# 3_AT_START_F403A_V1_2_PowerPeripherals.net
KiCad netlist of a schematic drawn in Altium Designer
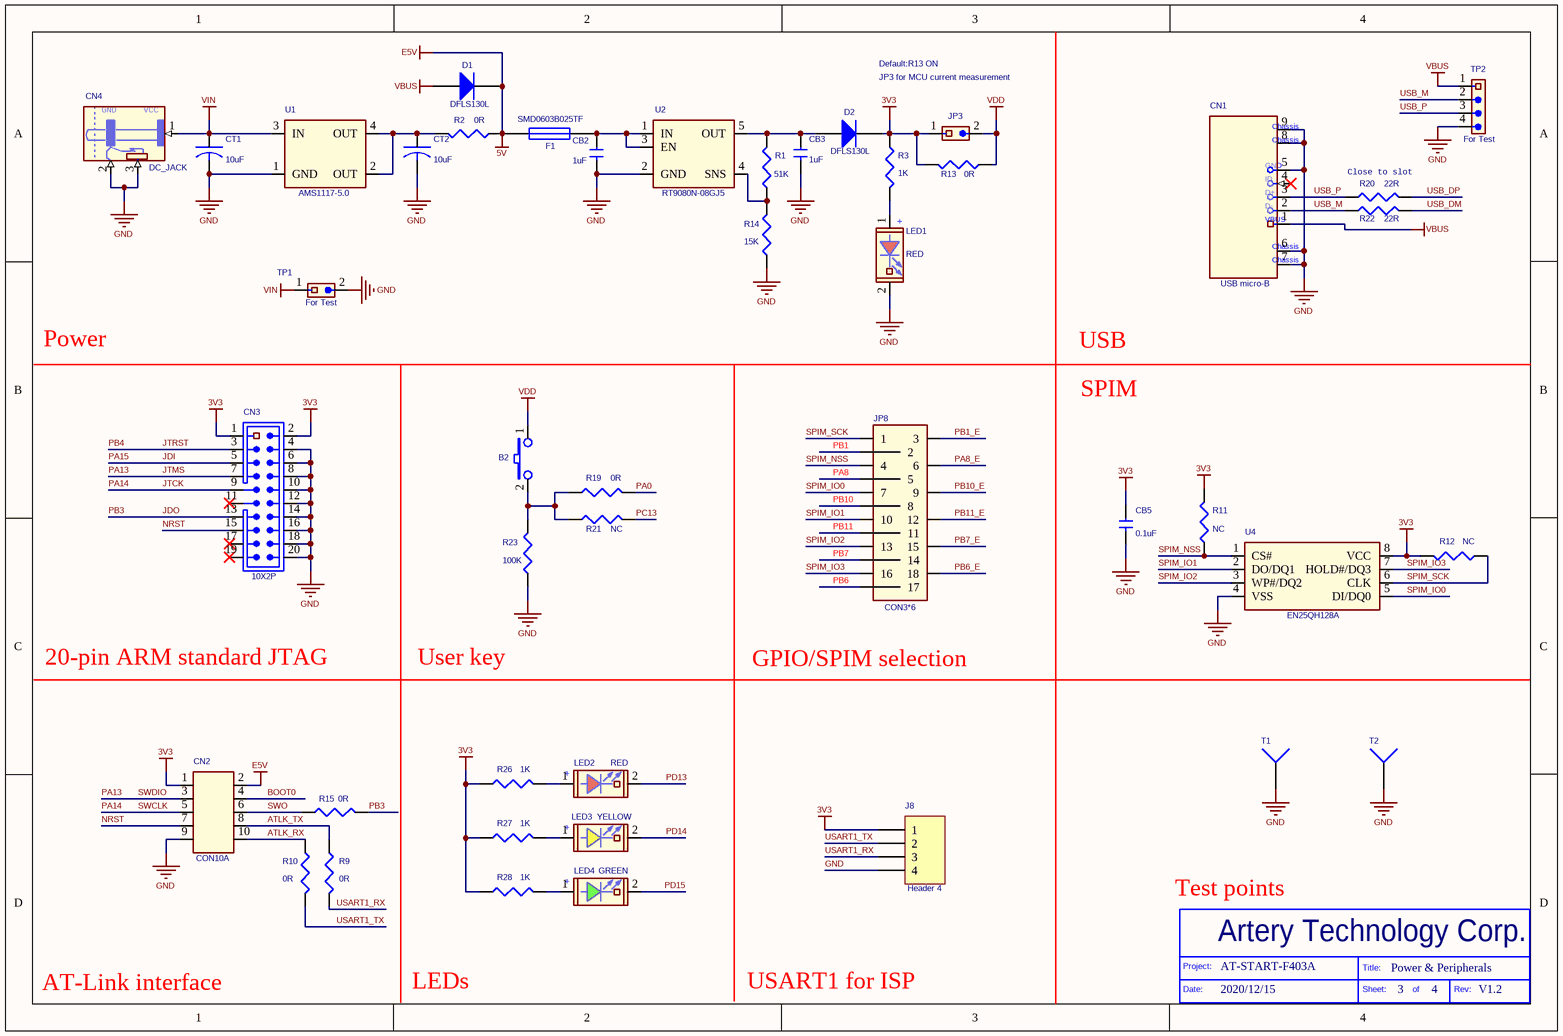
[diagram p0: 3_AT_START_F403A_V1.2_PowerPeripherals.SchDoc]

(export (version "E")
  (design (tool "Eeschema 10.0.6"))
  (components
    (comp (ref "B2") (value "PB,Blue,SMD_2P") (libsource (lib "*") (part "Push_Bottom,Blue,SMD_2P")))
    (comp (ref "CB2") (value "1uF") (libsource (lib "*") (part "0.1uF,50V,20%,SMD0603")))
    (comp (ref "CB3") (value "1uF") (libsource (lib "*") (part "0.1uF,50V,20%,SMD0603")))
    (comp (ref "CB5") (value "0.1uF") (libsource (lib "*") (part "10uF,10V,10%,SMD0603")))
    (comp (ref "CN1") (value "USB micro-B") (libsource (lib "*") (part "USB_miniAB,SMD_0")))
    (comp (ref "CN2") (value "CON10A") (footprint "HDR2X5") (libsource (lib "*") (part "CON10A_0")))
    (comp (ref "CN3") (value "10X2P") (libsource (lib "*") (part "10x2P,Male,Housing,DIP_2.54")))
    (comp (ref "CN4") (value "DC_JACK") (libsource (lib "*") (part "DC12V_Power_JACK,2.0,DIP_3P")))
    (comp (ref "CT1")
      (value "10uF")
      (description "10uF,10%,25V")
      (libsource (lib "*") (part "10uF,16V,20%,B_Case_Dup1"))
    )
    (comp (ref "CT2")
      (value "10uF")
      (description "10uF,10%,25V")
      (libsource (lib "*") (part "10uF,16V,20%,B_Case_Dup1"))
    )
    (comp (ref "D1")
      (value "DFLS130L")
      (footprint "SOD-123")
      (description "Default Diode")
      (fields (field (name "PUBLISHER") "Altium Limited"))
      (libsource (lib "Miscellaneous Devices") (part "Diode"))
    )
    (comp (ref "D2")
      (value "DFLS130L")
      (footprint "SOD-123")
      (description "Default Diode")
      (fields (field (name "PUBLISHER") "Altium Limited"))
      (libsource (lib "Miscellaneous Devices") (part "Diode"))
    )
    (comp (ref "F1")
      (value "SMD0603B025TF")
      (footprint "r0603")
      (description "Fuse")
      (fields (field (name "PUBLISHER") "Altium Limited"))
      (libsource (lib "Miscellaneous Devices") (part "Fuse 1"))
    )
    (comp (ref "J8")
      (value "Header 4")
      (footprint "HDR1X4")
      (description "Header, 4-Pin")
      (fields (field (name "PUBLISHER") "Altium Limited"))
      (libsource (lib "Miscellaneous Connectors") (part "Header 4"))
    )
    (comp (ref "JP3")
      (value "1X2P_2.54M")
      (footprint "HDR1X2")
      (libsource (lib "*") (part "1X2P,Male,DIP_2.54"))
    )
    (comp (ref "JP8")
      (value "CON3*6")
      (footprint "HDR3X6")
      (libsource (lib "SCM_START_402F") (part "CON3*6"))
    )
    (comp (ref "LED1") (value "RED") (footprint "LED0603") (libsource (lib "") (part "RED,SMD0603_1")))
    (comp (ref "LED2")
      (value "RED")
      (footprint "LED0603")
      (libsource (lib "AT32F403_TINY_LQFP144_Library") (part "RED,SMD0603"))
    )
    (comp (ref "LED3")
      (value "YELLOW")
      (footprint "LED0603")
      (libsource (lib "Schlib1") (part "YELLOW,SMD0603"))
    )
    (comp (ref "LED4")
      (value "GREEN")
      (footprint "LED0603")
      (libsource (lib "AT32F403_TINY_LQFP144_Library") (part "GREEN,SMD0603"))
    )
    (comp (ref "R1") (value "51K") (libsource (lib "*") (part "470,1/10W,1%,SMD0603")))
    (comp (ref "R2") (value "0R") (libsource (lib "*") (part "470,1/10W,1%,SMD0603")))
    (comp (ref "R3") (value "1K") (libsource (lib "*") (part "470,1/10W,1%,SMD0603")))
    (comp (ref "R9") (value "0R") (libsource (lib "*") (part "470,1/10W,1%,SMD0603")))
    (comp (ref "R10") (value "0R") (libsource (lib "*") (part "470,1/10W,1%,SMD0603")))
    (comp (ref "R11") (value "NC") (libsource (lib "*") (part "47K,1/10W,1%,SMD0603")))
    (comp (ref "R12") (value "NC") (libsource (lib "*") (part "47K,1/10W,1%,SMD0603")))
    (comp (ref "R13") (value "0R") (libsource (lib "*") (part "470,1/10W,1%,SMD0603")))
    (comp (ref "R14") (value "15K") (libsource (lib "*") (part "470,1/10W,1%,SMD0603")))
    (comp (ref "R15") (value "0R") (libsource (lib "*") (part "470,1/10W,1%,SMD0603")))
    (comp (ref "R19") (value "0R") (libsource (lib "*") (part "470,1/10W,1%,SMD0603")))
    (comp (ref "R20") (value "22R") (libsource (lib "*") (part "22,1/10W,1%,SMD0603")))
    (comp (ref "R21") (value "NC") (libsource (lib "*") (part "470,1/10W,1%,SMD0603")))
    (comp (ref "R22") (value "22R") (libsource (lib "*") (part "22,1/10W,1%,SMD0603")))
    (comp (ref "R23") (value "100K") (libsource (lib "*") (part "10K,1/10W,1%,SMD0603")))
    (comp (ref "R26") (value "1K") (libsource (lib "*") (part "470,1/10W,1%,SMD0603")))
    (comp (ref "R27") (value "1K") (libsource (lib "*") (part "470,1/10W,1%,SMD0603")))
    (comp (ref "R28") (value "1K") (libsource (lib "*") (part "470,1/10W,1%,SMD0603")))
    (comp (ref "T1")
      (value "Socket")
      (footprint "TestPoint")
      (fields (field (name "PUBLISHER") "Altium Limited"))
      (libsource (lib "Miscellaneous Connectors") (part "Socket"))
    )
    (comp (ref "T2")
      (value "Socket")
      (footprint "TestPoint")
      (fields (field (name "PUBLISHER") "Altium Limited"))
      (libsource (lib "Miscellaneous Connectors") (part "Socket"))
    )
    (comp (ref "TP1")
      (value "1X2P_2.54M")
      (footprint "HDR1X2 - SOP")
      (libsource (lib "*") (part "1X2P,Male,DIP_2.54"))
    )
    (comp (ref "TP2")
      (value "1X4P_2.54F")
      (footprint "HDR1X4 - top")
      (libsource (lib "*") (part "1X4P,Female,DIP_2.54"))
    )
    (comp (ref "U1") (value "AMS1117-5.0") (libsource (lib "*") (part "AMS1117-3.3")))
    (comp (ref "U2") (value "RT9080N-08GJ5") (libsource (lib "SCM_START_402F") (part "RT9080N")))
    (comp (ref "U4")
      (value "EN25QH128A")
      (footprint "SOIC8_208")
      (libsource (lib "AT32F403_TINY_LQFP144_Library") (part "W25Q128FVSIQ,SOIC8_1"))
    )
  )
  (nets
    (net (code "1") (name "/ATLK_RX") (class "Default")
      (node (ref "CN2") (pin "10") (pinfunction "10_10") (pintype "passive"))
      (node (ref "R10") (pin "1") (pinfunction "1_1") (pintype "passive"))
    )
    (net (code "2") (name "/ATLK_TX") (class "Default")
      (node (ref "CN2") (pin "8") (pinfunction "8_8") (pintype "passive"))
      (node (ref "R9") (pin "1") (pinfunction "1_1") (pintype "passive"))
    )
    (net (code "3") (name "/BOOT0") (class "Default")
      (node (ref "CN2") (pin "4") (pinfunction "4_4") (pintype "passive"))
    )
    (net (code "4") (name "/JDI") (class "Default")
      (node (ref "CN3") (pin "5") (pinfunction "5_5") (pintype "passive"))
    )
    (net (code "5") (name "/JDO") (class "Default")
      (node (ref "CN3") (pin "13") (pinfunction "13_13") (pintype "passive"))
      (node (ref "R15") (pin "2") (pinfunction "2_2") (pintype "passive"))
    )
    (net (code "6") (name "/JTCK") (class "Default")
      (node (ref "CN2") (pin "5") (pinfunction "5_5") (pintype "passive"))
      (node (ref "CN3") (pin "9") (pinfunction "9_9") (pintype "passive"))
    )
    (net (code "7") (name "/JTMS") (class "Default")
      (node (ref "CN2") (pin "3") (pinfunction "3_3") (pintype "passive"))
      (node (ref "CN3") (pin "7") (pinfunction "7_7") (pintype "passive"))
    )
    (net (code "8") (name "/JTRST") (class "Default")
      (node (ref "CN3") (pin "3") (pinfunction "3_3") (pintype "passive"))
    )
    (net (code "9") (name "/NRST") (class "Default")
      (node (ref "CN2") (pin "7") (pinfunction "7_7") (pintype "passive"))
      (node (ref "CN3") (pin "15") (pinfunction "15_15") (pintype "passive"))
    )
    (net (code "10") (name "/PA0") (class "Default")
      (node (ref "R19") (pin "2") (pinfunction "2_2") (pintype "passive"))
    )
    (net (code "11") (name "/PA8") (class "Default")
      (node (ref "JP8") (pin "5") (pinfunction "5_5") (pintype "passive"))
    )
    (net (code "12") (name "/PA8_E") (class "Default")
      (node (ref "JP8") (pin "6") (pinfunction "6_6") (pintype "passive"))
    )
    (net (code "13") (name "/PB1") (class "Default")
      (node (ref "JP8") (pin "2") (pinfunction "2_2") (pintype "passive"))
    )
    (net (code "14") (name "/PB1_E") (class "Default")
      (node (ref "JP8") (pin "3") (pinfunction "3_3") (pintype "passive"))
    )
    (net (code "15") (name "/PB6") (class "Default")
      (node (ref "JP8") (pin "17") (pinfunction "17_17") (pintype "passive"))
    )
    (net (code "16") (name "/PB6_E") (class "Default")
      (node (ref "JP8") (pin "18") (pinfunction "18_18") (pintype "passive"))
    )
    (net (code "17") (name "/PB7") (class "Default")
      (node (ref "JP8") (pin "14") (pinfunction "14_14") (pintype "passive"))
    )
    (net (code "18") (name "/PB7_E") (class "Default")
      (node (ref "JP8") (pin "15") (pinfunction "15_15") (pintype "passive"))
    )
    (net (code "19") (name "/PB10") (class "Default")
      (node (ref "JP8") (pin "8") (pinfunction "8_8") (pintype "passive"))
    )
    (net (code "20") (name "/PB10_E") (class "Default")
      (node (ref "JP8") (pin "9") (pinfunction "9_9") (pintype "passive"))
    )
    (net (code "21") (name "/PB11") (class "Default")
      (node (ref "JP8") (pin "11") (pinfunction "11_11") (pintype "passive"))
    )
    (net (code "22") (name "/PB11_E") (class "Default")
      (node (ref "JP8") (pin "12") (pinfunction "12_12") (pintype "passive"))
    )
    (net (code "23") (name "/PC13") (class "Default")
      (node (ref "R21") (pin "2") (pinfunction "2_2") (pintype "passive"))
    )
    (net (code "24") (name "/PD13") (class "Default")
      (node (ref "LED2") (pin "2") (pinfunction "CATHODE_2") (pintype "passive"))
    )
    (net (code "25") (name "/PD14") (class "Default")
      (node (ref "LED3") (pin "2") (pinfunction "CATHODE_2") (pintype "passive"))
    )
    (net (code "26") (name "/PD15") (class "Default")
      (node (ref "LED4") (pin "2") (pinfunction "CATHODE_2") (pintype "passive"))
    )
    (net (code "27") (name "/SPIM_IO0") (class "Default")
      (node (ref "JP8") (pin "7") (pinfunction "7_7") (pintype "passive"))
      (node (ref "U4") (pin "5") (pinfunction "DI/DQ0_5") (pintype "passive"))
    )
    (net (code "28") (name "/SPIM_IO1") (class "Default")
      (node (ref "JP8") (pin "10") (pinfunction "10_10") (pintype "passive"))
      (node (ref "U4") (pin "2") (pinfunction "DO/DQ1_2") (pintype "passive"))
    )
    (net (code "29") (name "/SPIM_IO2") (class "Default")
      (node (ref "JP8") (pin "13") (pinfunction "13_13") (pintype "passive"))
      (node (ref "U4") (pin "3") (pinfunction "WP#/DQ2_3") (pintype "passive"))
    )
    (net (code "30") (name "/SPIM_IO3") (class "Default")
      (node (ref "JP8") (pin "16") (pinfunction "16_16") (pintype "passive"))
      (node (ref "U4") (pin "7") (pinfunction "HOLD#/DQ3_7") (pintype "passive"))
    )
    (net (code "31") (name "/SPIM_NSS") (class "Default")
      (node (ref "JP8") (pin "4") (pinfunction "4_4") (pintype "passive"))
      (node (ref "R11") (pin "1") (pinfunction "1_1") (pintype "passive"))
      (node (ref "U4") (pin "1") (pinfunction "CS#_1") (pintype "passive"))
    )
    (net (code "32") (name "/SPIM_SCK") (class "Default")
      (node (ref "JP8") (pin "1") (pinfunction "1_1") (pintype "passive"))
      (node (ref "R12") (pin "1") (pinfunction "1_1") (pintype "passive"))
      (node (ref "U4") (pin "6") (pinfunction "CLK_6") (pintype "passive"))
    )
    (net (code "33") (name "/SWO") (class "Default")
      (node (ref "CN2") (pin "6") (pinfunction "6_6") (pintype "passive"))
      (node (ref "R15") (pin "1") (pinfunction "1_1") (pintype "passive"))
    )
    (net (code "34") (name "/USART1_RX") (class "Default")
      (node (ref "J8") (pin "3") (pinfunction "3_3") (pintype "passive"))
      (node (ref "R9") (pin "2") (pinfunction "2_2") (pintype "passive"))
    )
    (net (code "35") (name "/USART1_TX") (class "Default")
      (node (ref "J8") (pin "2") (pinfunction "2_2") (pintype "passive"))
      (node (ref "R10") (pin "2") (pinfunction "2_2") (pintype "passive"))
    )
    (net (code "36") (name "/USB_DM") (class "Default")
      (node (ref "R22") (pin "2") (pinfunction "2_2") (pintype "passive"))
    )
    (net (code "37") (name "/USB_DP") (class "Default")
      (node (ref "R20") (pin "2") (pinfunction "2_2") (pintype "passive"))
    )
    (net (code "38") (name "/USB_M") (class "Default")
      (node (ref "CN1") (pin "2") (pinfunction "D-_2") (pintype "bidirectional"))
      (node (ref "R22") (pin "1") (pinfunction "1_1") (pintype "passive"))
      (node (ref "TP2") (pin "2") (pinfunction "2_2") (pintype "passive"))
    )
    (net (code "39") (name "/USB_P") (class "Default")
      (node (ref "CN1") (pin "3") (pinfunction "D+_3") (pintype "bidirectional"))
      (node (ref "R20") (pin "1") (pinfunction "1_1") (pintype "passive"))
      (node (ref "TP2") (pin "3") (pinfunction "3_3") (pintype "passive"))
    )
    (net (code "40") (name "3V3") (class "Default")
      (node (ref "CB5") (pin "1") (pinfunction "1_1") (pintype "passive"))
      (node (ref "CN2") (pin "1") (pinfunction "1_1") (pintype "passive"))
      (node (ref "CN3") (pin "1") (pinfunction "1_1") (pintype "passive"))
      (node (ref "CN3") (pin "2") (pinfunction "2_2") (pintype "passive"))
      (node (ref "D2") (pin "2") (pinfunction "K_2") (pintype "passive"))
      (node (ref "J8") (pin "1") (pinfunction "1_1") (pintype "passive"))
      (node (ref "JP3") (pin "1") (pinfunction "1_1") (pintype "passive"))
      (node (ref "R11") (pin "2") (pinfunction "2_2") (pintype "passive"))
      (node (ref "R12") (pin "2") (pinfunction "2_2") (pintype "passive"))
      (node (ref "R13") (pin "2") (pinfunction "2_2") (pintype "passive"))
      (node (ref "R26") (pin "1") (pinfunction "1_1") (pintype "passive"))
      (node (ref "R27") (pin "1") (pinfunction "1_1") (pintype "passive"))
      (node (ref "R28") (pin "1") (pinfunction "1_1") (pintype "passive"))
      (node (ref "R3") (pin "1") (pinfunction "1_1") (pintype "passive"))
      (node (ref "U4") (pin "8") (pinfunction "VCC_8") (pintype "power_in"))
    )
    (net (code "41") (name "5V") (class "Default")
      (node (ref "CN2") (pin "2") (pinfunction "2_2") (pintype "passive"))
      (node (ref "D1") (pin "2") (pinfunction "K_2") (pintype "passive"))
      (node (ref "F1") (pin "1") (pinfunction "1_1") (pintype "passive"))
      (node (ref "R2") (pin "1") (pinfunction "1_1") (pintype "passive"))
    )
    (net (code "42") (name "GND") (class "Default")
      (node (ref "CB2") (pin "2") (pinfunction "2_2") (pintype "passive"))
      (node (ref "CB3") (pin "2") (pinfunction "2_2") (pintype "passive"))
      (node (ref "CB5") (pin "2") (pinfunction "2_2") (pintype "passive"))
      (node (ref "CN1") (pin "5") (pinfunction "GND_5") (pintype "passive"))
      (node (ref "CN1") (pin "6") (pinfunction "6_6") (pintype "passive"))
      (node (ref "CN1") (pin "7") (pinfunction "7_7") (pintype "passive"))
      (node (ref "CN1") (pin "8") (pinfunction "8_8") (pintype "passive"))
      (node (ref "CN1") (pin "9") (pinfunction "9_9") (pintype "passive"))
      (node (ref "CN2") (pin "9") (pinfunction "9_9") (pintype "passive"))
      (node (ref "CN3") (pin "10") (pinfunction "10_10") (pintype "passive"))
      (node (ref "CN3") (pin "12") (pinfunction "12_12") (pintype "passive"))
      (node (ref "CN3") (pin "14") (pinfunction "14_14") (pintype "passive"))
      (node (ref "CN3") (pin "16") (pinfunction "16_16") (pintype "passive"))
      (node (ref "CN3") (pin "18") (pinfunction "18_18") (pintype "passive"))
      (node (ref "CN3") (pin "20") (pinfunction "20_20") (pintype "passive"))
      (node (ref "CN3") (pin "4") (pinfunction "4_4") (pintype "passive"))
      (node (ref "CN3") (pin "6") (pinfunction "6_6") (pintype "passive"))
      (node (ref "CN3") (pin "8") (pinfunction "8_8") (pintype "passive"))
      (node (ref "CN4") (pin "2") (pinfunction "2_2") (pintype "input"))
      (node (ref "CN4") (pin "3") (pinfunction "3_3") (pintype "input"))
      (node (ref "CT1") (pin "2") (pinfunction "2_2") (pintype "passive"))
      (node (ref "CT2") (pin "2") (pinfunction "2_2") (pintype "passive"))
      (node (ref "J8") (pin "4") (pinfunction "4_4") (pintype "passive"))
      (node (ref "LED1") (pin "2") (pinfunction "CATHODE_2") (pintype "passive"))
      (node (ref "R14") (pin "1") (pinfunction "1_1") (pintype "passive"))
      (node (ref "R23") (pin "1") (pinfunction "1_1") (pintype "passive"))
      (node (ref "T1") (pin "1") (pinfunction "1_1") (pintype "passive"))
      (node (ref "T2") (pin "1") (pinfunction "1_1") (pintype "passive"))
      (node (ref "TP1") (pin "2") (pinfunction "2_2") (pintype "passive"))
      (node (ref "TP2") (pin "4") (pinfunction "4_4") (pintype "passive"))
      (node (ref "U1") (pin "1") (pinfunction "GND_1") (pintype "passive"))
      (node (ref "U2") (pin "2") (pinfunction "GND_2") (pintype "power_in"))
      (node (ref "U4") (pin "4") (pinfunction "VSS_4") (pintype "power_in"))
    )
    (net (code "43") (name "Net-(B2-Pad2)") (class "Default")
      (node (ref "B2") (pin "2") (pinfunction "2_2") (pintype "passive"))
      (node (ref "R19") (pin "1") (pinfunction "1_1") (pintype "passive"))
      (node (ref "R21") (pin "1") (pinfunction "1_1") (pintype "passive"))
      (node (ref "R23") (pin "2") (pinfunction "2_2") (pintype "passive"))
    )
    (net (code "44") (name "Net-(CT2-Pad1)") (class "Default")
      (node (ref "CT2") (pin "1") (pinfunction "1_1") (pintype "passive"))
      (node (ref "R2") (pin "2") (pinfunction "2_2") (pintype "passive"))
      (node (ref "U1") (pin "2") (pinfunction "OUT_2") (pintype "passive"))
      (node (ref "U1") (pin "4") (pinfunction "OUT_4") (pintype "passive"))
    )
    (net (code "45") (name "Net-(D2-A)") (class "Default")
      (node (ref "CB3") (pin "1") (pinfunction "1_1") (pintype "passive"))
      (node (ref "D2") (pin "1") (pinfunction "A_1") (pintype "passive"))
      (node (ref "R1") (pin "2") (pinfunction "2_2") (pintype "passive"))
      (node (ref "U2") (pin "5") (pinfunction "OUT_5") (pintype "power_in"))
    )
    (net (code "46") (name "Net-(LED1-ANODE)") (class "Default")
      (node (ref "LED1") (pin "1") (pinfunction "ANODE_1") (pintype "passive"))
      (node (ref "R3") (pin "2") (pinfunction "2_2") (pintype "passive"))
    )
    (net (code "47") (name "Net-(LED2-ANODE)") (class "Default")
      (node (ref "LED2") (pin "1") (pinfunction "ANODE_1") (pintype "passive"))
      (node (ref "R26") (pin "2") (pinfunction "2_2") (pintype "passive"))
    )
    (net (code "48") (name "Net-(LED3-ANODE)") (class "Default")
      (node (ref "LED3") (pin "1") (pinfunction "ANODE_1") (pintype "passive"))
      (node (ref "R27") (pin "2") (pinfunction "2_2") (pintype "passive"))
    )
    (net (code "49") (name "Net-(LED4-ANODE)") (class "Default")
      (node (ref "LED4") (pin "1") (pinfunction "ANODE_1") (pintype "passive"))
      (node (ref "R28") (pin "2") (pinfunction "2_2") (pintype "passive"))
    )
    (net (code "50") (name "Net-(U2-EN)") (class "Default")
      (node (ref "CB2") (pin "1") (pinfunction "1_1") (pintype "passive"))
      (node (ref "F1") (pin "2") (pinfunction "2_2") (pintype "passive"))
      (node (ref "U2") (pin "1") (pinfunction "IN_1") (pintype "power_in"))
      (node (ref "U2") (pin "3") (pinfunction "EN_3") (pintype "passive"))
    )
    (net (code "51") (name "Net-(U2-SNS)") (class "Default")
      (node (ref "R1") (pin "1") (pinfunction "1_1") (pintype "passive"))
      (node (ref "R14") (pin "2") (pinfunction "2_2") (pintype "passive"))
      (node (ref "U2") (pin "4") (pinfunction "SNS_4") (pintype "passive"))
    )
    (net (code "52") (name "VBUS") (class "Default")
      (node (ref "CN1") (pin "1") (pinfunction "VBUS_1") (pintype "passive"))
      (node (ref "D1") (pin "1") (pinfunction "A_1") (pintype "passive"))
      (node (ref "TP2") (pin "1") (pinfunction "1_1") (pintype "passive"))
    )
    (net (code "53") (name "VDD") (class "Default")
      (node (ref "B2") (pin "1") (pinfunction "1_1") (pintype "passive"))
      (node (ref "JP3") (pin "2") (pinfunction "2_2") (pintype "passive"))
      (node (ref "R13") (pin "1") (pinfunction "1_1") (pintype "passive"))
    )
    (net (code "54") (name "VIN") (class "Default")
      (node (ref "CN4") (pin "1") (pinfunction "1_1") (pintype "input"))
      (node (ref "CT1") (pin "1") (pinfunction "1_1") (pintype "passive"))
      (node (ref "TP1") (pin "1") (pinfunction "1_1") (pintype "passive"))
      (node (ref "U1") (pin "3") (pinfunction "IN_3") (pintype "passive"))
    )
    (net (code "55") (name "unconnected-(CN1-ID-Pad4)") (class "Default")
      (node (ref "CN1") (pin "4") (pinfunction "ID_4") (pintype "input+no_connect"))
    )
    (net (code "56") (name "unconnected-(CN3-Pad11)") (class "Default")
      (node (ref "CN3") (pin "11") (pinfunction "11_11") (pintype "passive+no_connect"))
    )
    (net (code "57") (name "unconnected-(CN3-Pad17)") (class "Default")
      (node (ref "CN3") (pin "17") (pinfunction "17_17") (pintype "passive+no_connect"))
    )
    (net (code "58") (name "unconnected-(CN3-Pad19)") (class "Default")
      (node (ref "CN3") (pin "19") (pinfunction "19_19") (pintype "passive+no_connect"))
    )
  )
)
